# CATS_GS-Radio.net
KiCad netlist of a schematic drawn in Altium Designer
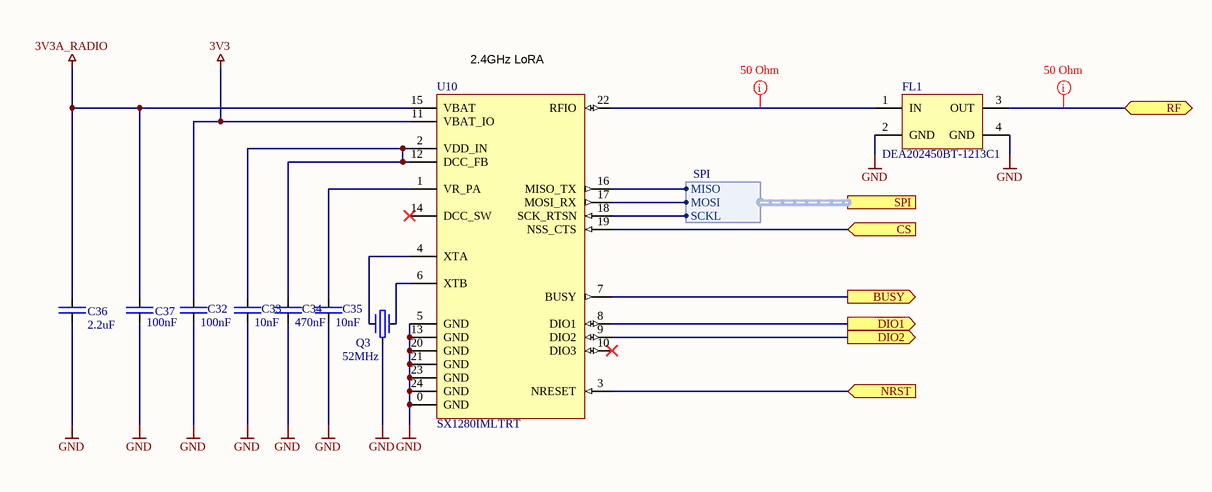
[diagram p0: CATS_GS-Radio.SchDoc]

(export (version "E")
  (design (tool "Eeschema 10.0.6"))
  (components
    (comp (ref "C32")
      (value "100nF")
      (footprint "SMD Keramikkondensator 0402")
      (description "SMD Ceramic Capacitor E6")
      (libsource (lib "CATS-EUROC") (part "E6 - 100nF"))
    )
    (comp (ref "C33")
      (value "10nF")
      (footprint "SMD Keramikkondensator 0402")
      (description "SMD Ceramic Capacitor E6")
      (libsource (lib "CATS-EUROC") (part "E6 - 10nF"))
    )
    (comp (ref "C34")
      (value "470nF")
      (footprint "SMD Keramikkondensator 0402")
      (description "SMD Ceramic Capacitor E6")
      (libsource (lib "CATS-EUROC") (part "E6 - 470nF"))
    )
    (comp (ref "C35")
      (value "10nF")
      (footprint "SMD Keramikkondensator 0402")
      (description "SMD Ceramic Capacitor E6")
      (libsource (lib "CATS-EUROC") (part "E6 - 10nF"))
    )
    (comp (ref "C36")
      (value "2.2uF")
      (footprint "SMD Keramikkondensator 0402")
      (description "SMD Ceramic Capacitor E6")
      (libsource (lib "Ceramic Capacitors-E6") (part "E6 - 2.2uF"))
    )
    (comp (ref "C37")
      (value "100nF")
      (footprint "SMD Keramikkondensator 0402")
      (description "SMD Ceramic Capacitor E6")
      (libsource (lib "CATS-EUROC") (part "E6 - 100nF"))
    )
    (comp (ref "FL1")
      (value "DEA202450BT-1213C1")
      (footprint "SMD Filter DEA202450BT")
      (description "Multilayer Band Pass Filter 2400-2500MHz")
      (libsource (lib "RF") (part "DEA202450BT-1213C1"))
    )
    (comp (ref "Q3")
      (value "52MHz")
      (footprint "SMD Crystal 2520")
      (description "52Mhz Ceramic 2.5 x 2.0mm SMD 10pF 60Ω ±10ppm")
      (libsource (lib "Other") (part "Crystal 52MHz - 2520"))
    )
    (comp (ref "U10")
      (value "SX1280IMLTRT")
      (footprint "SMD IC QFN-24")
      (description "Long Range, Low Power, 2.4 GHz\r\nTransceiver with Ranging Capability")
      (libsource (lib "RF") (part "SX1280IMLTRT"))
    )
  )
  (nets
    (net (code "2") (name "/BUSY") (class "Default")
      (node (ref "U10") (pin "7") (pinfunction "BUSY_7") (pintype "output"))
    )
    (net (code "3") (name "/CS") (class "Default")
      (node (ref "U10") (pin "19") (pinfunction "NSS_CTS_19") (pintype "input"))
    )
    (net (code "4") (name "/DIO1") (class "Default")
      (node (ref "U10") (pin "8") (pinfunction "DIO1_8") (pintype "bidirectional"))
    )
    (net (code "5") (name "/DIO2") (class "Default")
      (node (ref "U10") (pin "9") (pinfunction "DIO2_9") (pintype "bidirectional"))
    )
    (net (code "6") (name "/MISO") (class "Default")
      (node (ref "U10") (pin "16") (pinfunction "MISO_TX_16") (pintype "output"))
    )
    (net (code "7") (name "/MOSI") (class "Default")
      (node (ref "U10") (pin "17") (pinfunction "MOSI_RX_17") (pintype "output"))
    )
    (net (code "8") (name "/NRST") (class "Default")
      (node (ref "U10") (pin "3") (pinfunction "NRESET_3") (pintype "input"))
    )
    (net (code "9") (name "/RF") (class "Default")
      (node (ref "FL1") (pin "3") (pinfunction "OUT_3") (pintype "passive"))
    )
    (net (code "10") (name "/SCKL") (class "Default")
      (node (ref "U10") (pin "18") (pinfunction "SCK_RTSN_18") (pintype "input"))
    )
    (net (code "12") (name "3V3") (class "Default")
      (node (ref "C32") (pin "2") (pinfunction "2_2") (pintype "passive"))
      (node (ref "U10") (pin "11") (pinfunction "VBAT_IO_11") (pintype "passive"))
    )
    (net (code "13") (name "3V3A_RADIO") (class "Default")
      (node (ref "C36") (pin "2") (pinfunction "2_2") (pintype "passive"))
      (node (ref "C37") (pin "2") (pinfunction "2_2") (pintype "passive"))
      (node (ref "U10") (pin "15") (pinfunction "VBAT_15") (pintype "passive"))
    )
    (net (code "14") (name "GND") (class "Default")
      (node (ref "C32") (pin "1") (pinfunction "1_1") (pintype "passive"))
      (node (ref "C33") (pin "1") (pinfunction "1_1") (pintype "passive"))
      (node (ref "C34") (pin "1") (pinfunction "1_1") (pintype "passive"))
      (node (ref "C35") (pin "1") (pinfunction "1_1") (pintype "passive"))
      (node (ref "C36") (pin "1") (pinfunction "1_1") (pintype "passive"))
      (node (ref "C37") (pin "1") (pinfunction "1_1") (pintype "passive"))
      (node (ref "FL1") (pin "2") (pinfunction "GND_2") (pintype "passive"))
      (node (ref "FL1") (pin "4") (pinfunction "GND_4") (pintype "passive"))
      (node (ref "Q3") (pin "3") (pinfunction "3_3") (pintype "power_in"))
      (node (ref "U10") (pin "0") (pinfunction "GND_0") (pintype "passive"))
      (node (ref "U10") (pin "13") (pinfunction "GND_13") (pintype "passive"))
      (node (ref "U10") (pin "20") (pinfunction "GND_20") (pintype "passive"))
      (node (ref "U10") (pin "21") (pinfunction "GND_21") (pintype "passive"))
      (node (ref "U10") (pin "23") (pinfunction "GND_23") (pintype "passive"))
      (node (ref "U10") (pin "24") (pinfunction "GND_24") (pintype "passive"))
      (node (ref "U10") (pin "5") (pinfunction "GND_5") (pintype "passive"))
    )
    (net (code "15") (name "Net-(FL1-IN)") (class "Default")
      (node (ref "FL1") (pin "1") (pinfunction "IN_1") (pintype "passive"))
      (node (ref "U10") (pin "22") (pinfunction "RFIO_22") (pintype "bidirectional"))
    )
    (net (code "16") (name "Net-(U10-DCC_FB)") (class "Default")
      (node (ref "C33") (pin "2") (pinfunction "2_2") (pintype "passive"))
      (node (ref "C34") (pin "2") (pinfunction "2_2") (pintype "passive"))
      (node (ref "U10") (pin "12") (pinfunction "DCC_FB_12") (pintype "passive"))
      (node (ref "U10") (pin "2") (pinfunction "VDD_IN_2") (pintype "passive"))
    )
    (net (code "17") (name "Net-(U10-VR_PA)") (class "Default")
      (node (ref "C35") (pin "2") (pinfunction "2_2") (pintype "passive"))
      (node (ref "U10") (pin "1") (pinfunction "VR_PA_1") (pintype "passive"))
    )
    (net (code "18") (name "Net-(U10-XTA)") (class "Default")
      (node (ref "Q3") (pin "1") (pinfunction "1_1") (pintype "passive"))
      (node (ref "U10") (pin "4") (pinfunction "XTA_4") (pintype "passive"))
    )
    (net (code "19") (name "Net-(U10-XTB)") (class "Default")
      (node (ref "Q3") (pin "2") (pinfunction "2_2") (pintype "passive"))
      (node (ref "U10") (pin "6") (pinfunction "XTB_6") (pintype "passive"))
    )
    (net (code "20") (name "unconnected-(U10-DCC_SW-Pad14)") (class "Default")
      (node (ref "U10") (pin "14") (pinfunction "DCC_SW_14") (pintype "passive+no_connect"))
    )
    (net (code "21") (name "unconnected-(U10-DIO3-Pad10)") (class "Default")
      (node (ref "U10") (pin "10") (pinfunction "DIO3_10") (pintype "bidirectional+no_connect"))
    )
  )
)
